# SCH_NFC-Card_2024-06-29.net
KiCad netlist of a schematic drawn in EasyEDA
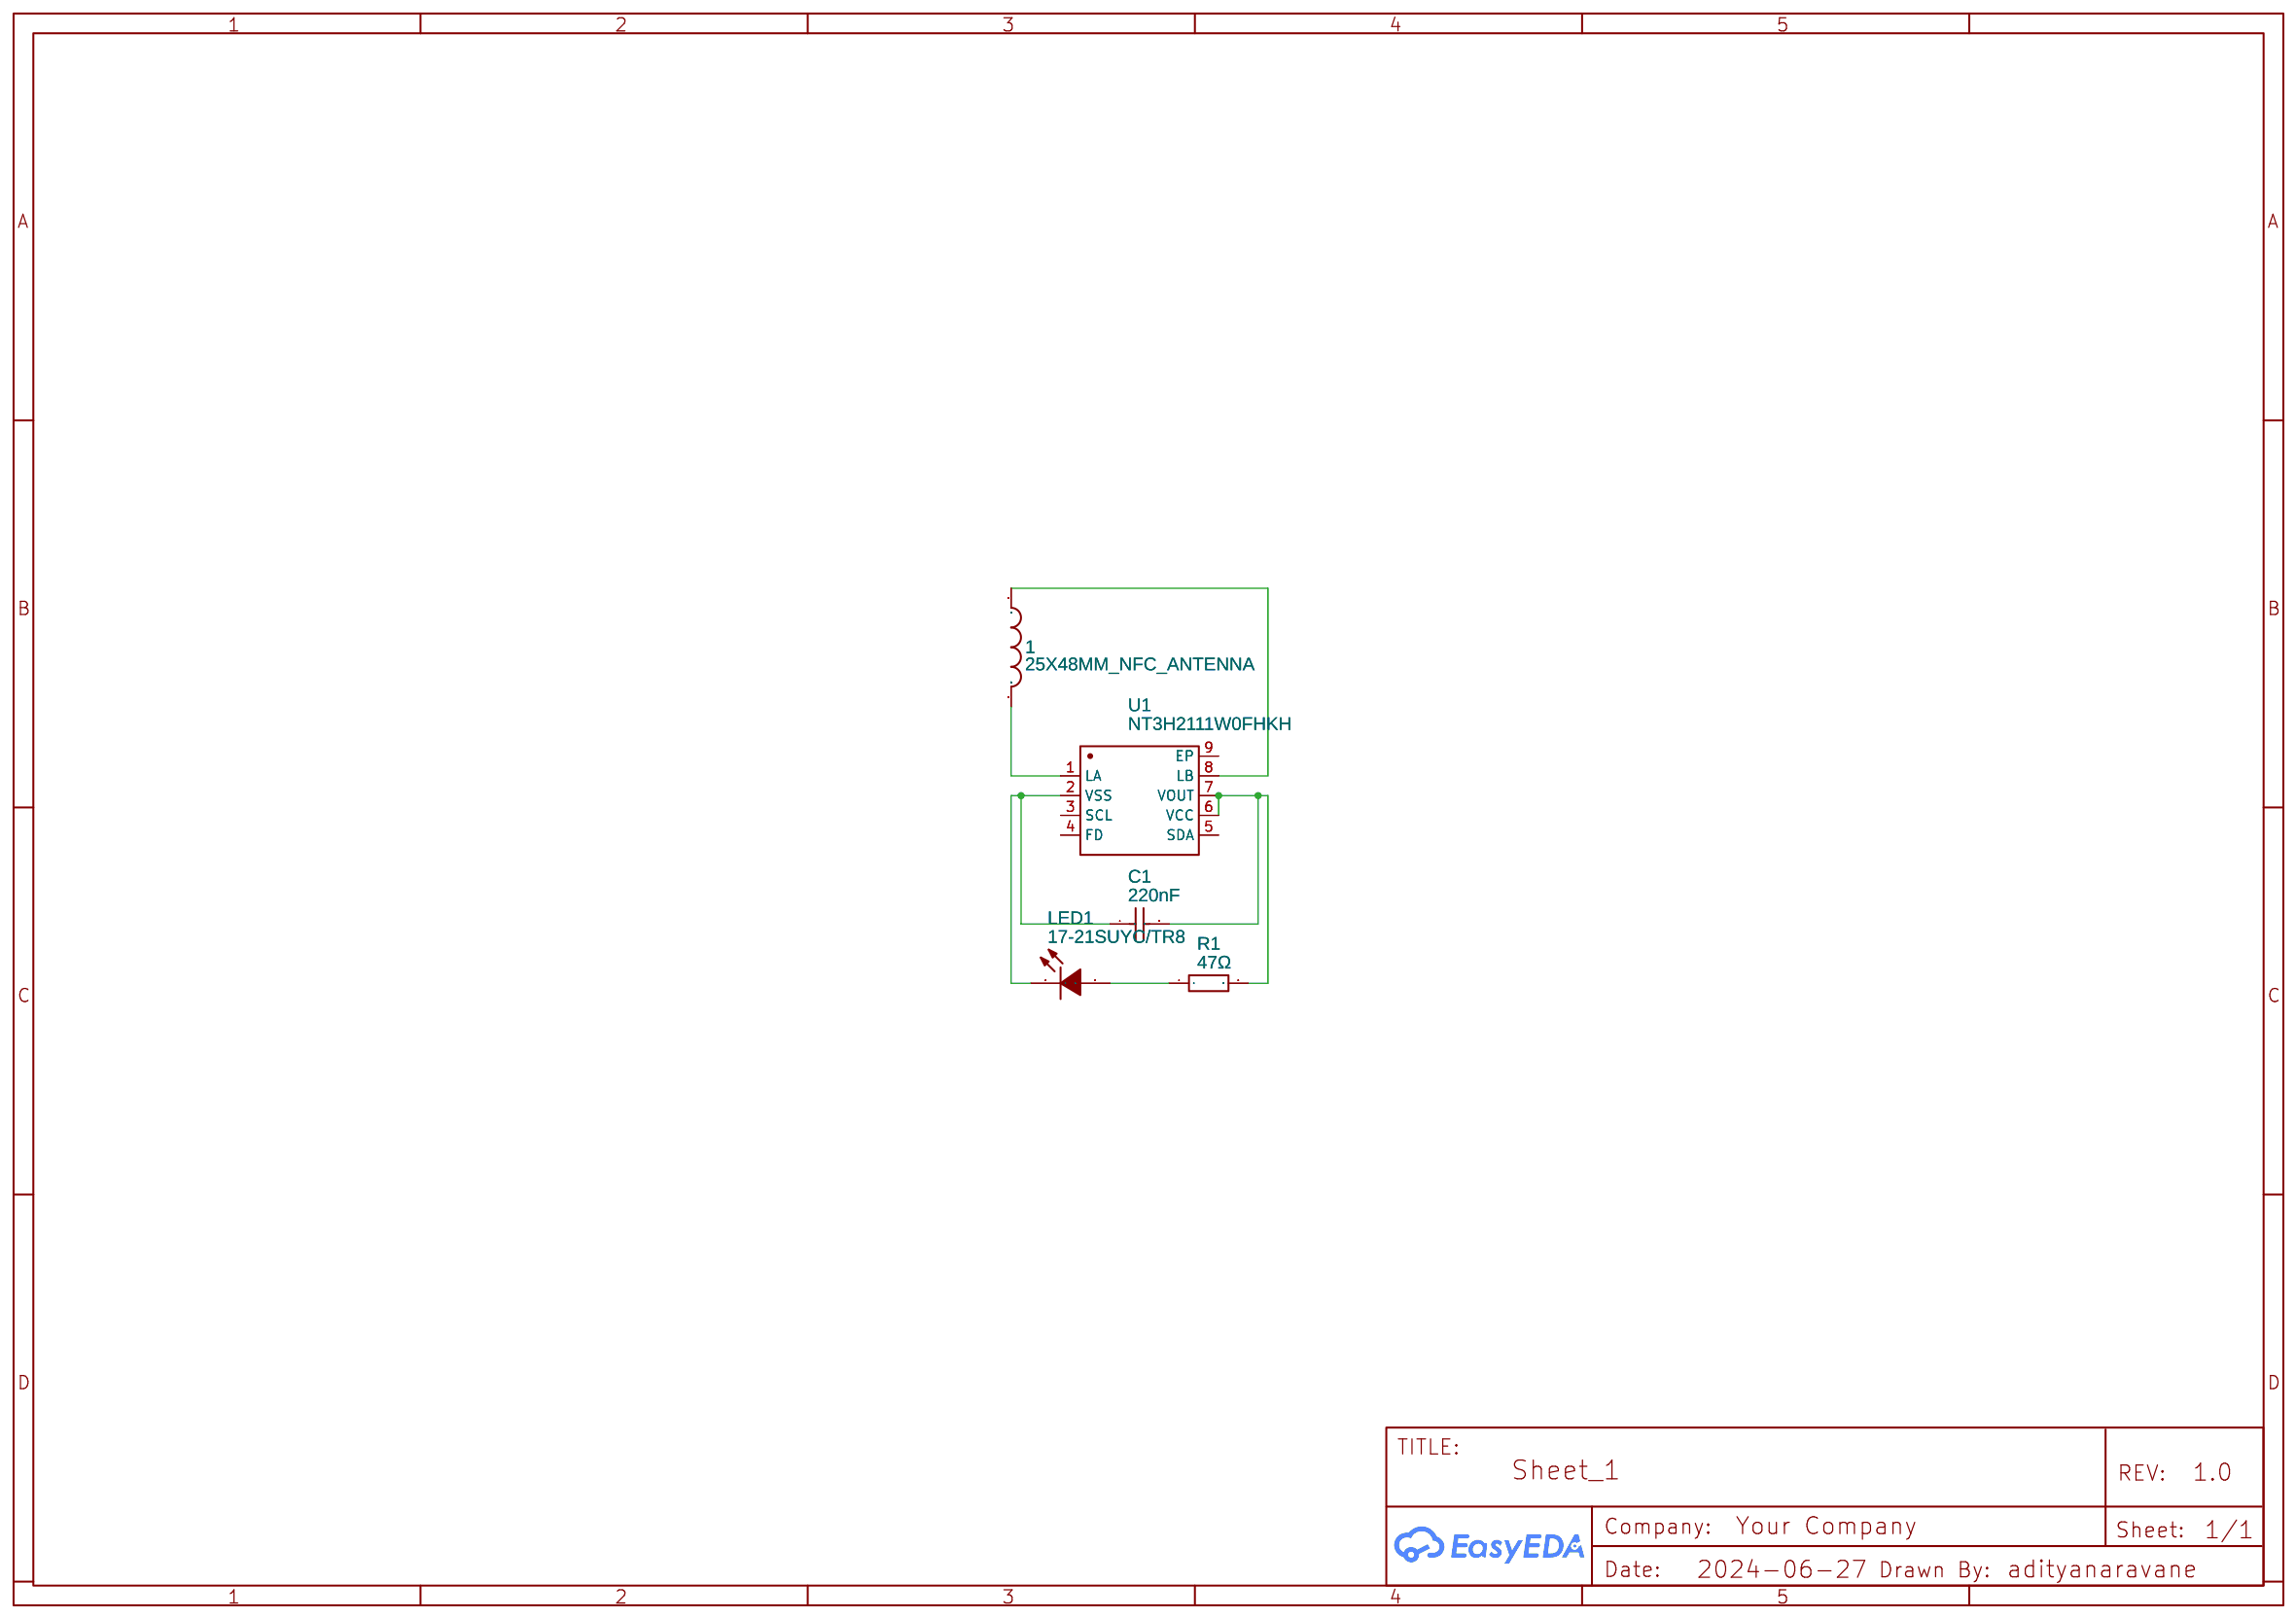
[diagram p0: schematic sheet]

(export (version "E")
  (design (tool "Eeschema 10.0.6"))
  (components
    (comp (ref "1") (value "25X48MM_NFC_ANTENNA") (libsource (lib "") (part "25X48MM_NFC_ANTENNA")))
    (comp (ref "C1")
      (value "220nF")
      (fields
        (field (name "Manufacturer Part") "CL10B224KA8NNNC")
        (field (name "Manufacturer") "SAMSUNG(三星)")
      )
      (libsource (lib "") (part "CL10B224KA8NNNC"))
    )
    (comp (ref "LED1")
      (value "17-21SUYC/TR8")
      (fields (field (name "Manufacturer Part") "KT-0805黄灯") (field (name "Manufacturer") "KENTO"))
      (libsource (lib "") (part "17-21SUYC/TR8"))
    )
    (comp (ref "R1")
      (value "47Ω")
      (fields
        (field (name "Manufacturer Part") "0603WAF470JT5E")
        (field (name "Manufacturer") "UNI-ROYAL(厚声)")
      )
      (libsource (lib "") (part "0603WAF470JT5E"))
    )
    (comp (ref "U1")
      (value "NT3H2111W0FHKH")
      (fields (field (name "Manufacturer") "NXP(恩智浦)"))
      (libsource (lib "") (part "NT3H2111W0FHKH"))
    )
  )
  (nets
    (net (code "1") (name "Net-(LED1-+)") (class "Default")
      (node (ref "LED1") (pin "1") (pinfunction "+_1") (pintype "unspecified"))
      (node (ref "R1") (pin "1") (pinfunction "1_1") (pintype "input"))
    )
    (net (code "2") (name "Net-(LED1--)") (class "Default")
      (node (ref "C1") (pin "1") (pinfunction "1_1") (pintype "input"))
      (node (ref "LED1") (pin "2") (pinfunction "-_2") (pintype "unspecified"))
      (node (ref "U1") (pin "2") (pinfunction "VSS_2") (pintype "unspecified"))
    )
    (net (code "3") (name "Net-(U1-LA)") (class "Default")
      (node (ref "1") (pin "P$2") (pinfunction "P$2_P$2") (pintype "bidirectional"))
      (node (ref "U1") (pin "1") (pinfunction "LA_1") (pintype "unspecified"))
    )
    (net (code "4") (name "Net-(U1-LB)") (class "Default")
      (node (ref "1") (pin "P$1") (pinfunction "P$1_P$1") (pintype "bidirectional"))
      (node (ref "U1") (pin "8") (pinfunction "LB_8") (pintype "unspecified"))
    )
    (net (code "5") (name "Net-(U1-VCC)") (class "Default")
      (node (ref "C1") (pin "2") (pinfunction "2_2") (pintype "input"))
      (node (ref "R1") (pin "2") (pinfunction "2_2") (pintype "input"))
      (node (ref "U1") (pin "6") (pinfunction "VCC_6") (pintype "unspecified"))
      (node (ref "U1") (pin "7") (pinfunction "VOUT_7") (pintype "unspecified"))
    )
    (net (code "6") (name "unconnected-(U1-EP-Pad9)") (class "Default")
      (node (ref "U1") (pin "9") (pinfunction "EP_9") (pintype "unspecified"))
    )
    (net (code "7") (name "unconnected-(U1-FD-Pad4)") (class "Default")
      (node (ref "U1") (pin "4") (pinfunction "FD_4") (pintype "unspecified"))
    )
    (net (code "8") (name "unconnected-(U1-SCL-Pad3)") (class "Default")
      (node (ref "U1") (pin "3") (pinfunction "SCL_3") (pintype "unspecified"))
    )
    (net (code "9") (name "unconnected-(U1-SDA-Pad5)") (class "Default")
      (node (ref "U1") (pin "5") (pinfunction "SDA_5") (pintype "unspecified"))
    )
  )
)
